# bot_base.net
KiCad netlist of a schematic drawn in EAGLE
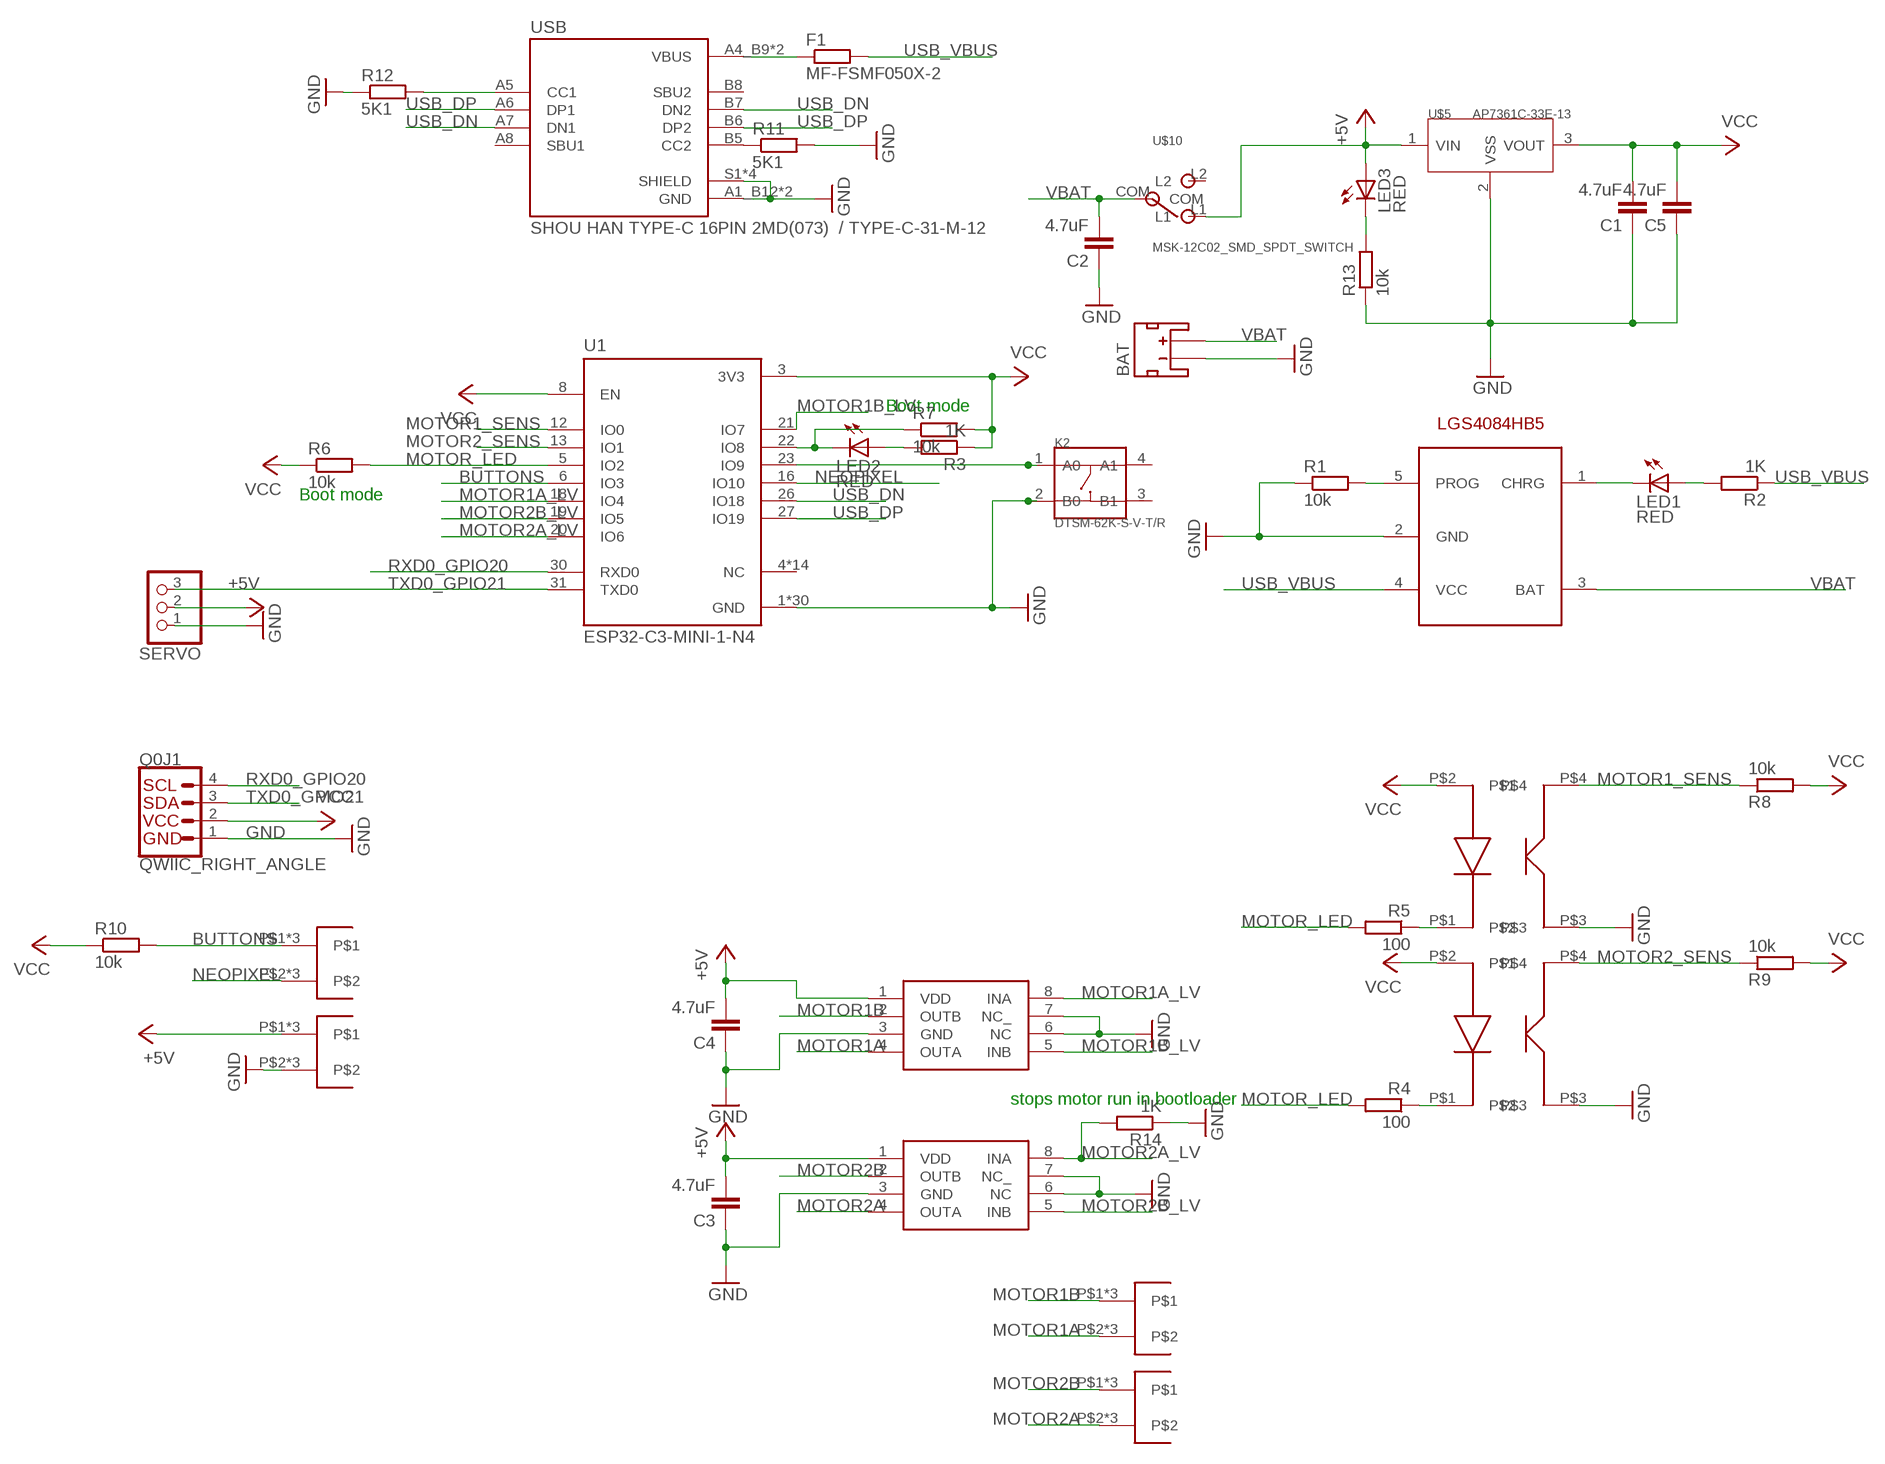
[diagram p0: schematic, sheet 1]

(export (version "E")
  (design (tool "Eeschema 10.0.6"))
  (components
    (comp (ref "BAT")
      (value "C47647 / S2B-PH-SM4-TB")
      (footprint "eagle-import:JST-2-SMD")
      (libsource (lib "eagle-import") (part "JST_2MM_MALE"))
    )
    (comp (ref "C1")
      (value "4.7uF")
      (footprint "eagle-import:C0805")
      (libsource (lib "eagle-import") (part "C-EUC0805"))
    )
    (comp (ref "C2")
      (value "4.7uF")
      (footprint "eagle-import:C0805")
      (libsource (lib "eagle-import") (part "C-EUC0805"))
    )
    (comp (ref "C3")
      (value "4.7uF")
      (footprint "eagle-import:C0805")
      (libsource (lib "eagle-import") (part "C-EUC0805"))
    )
    (comp (ref "C4")
      (value "4.7uF")
      (footprint "eagle-import:C0805")
      (libsource (lib "eagle-import") (part "C-EUC0805"))
    )
    (comp (ref "C5")
      (value "4.7uF")
      (footprint "eagle-import:C0805")
      (libsource (lib "eagle-import") (part "C-EUC0805"))
    )
    (comp (ref "F1")
      (value "MF-FSMF050X-2")
      (footprint "eagle-import:R0603")
      (libsource (lib "eagle-import") (part "R-EU_R0603"))
    )
    (comp (ref "K2")
      (value "DTSM-62K-S-V-T/R")
      (footprint "eagle-import:SW4-SMD-6.0X6.0X5.0MM")
      (libsource (lib "eagle-import") (part "SMD-SWITCH-TACTILE-SPST-NO(4P-D6.0MM)"))
    )
    (comp (ref "LED1")
      (value "RED")
      (footprint "eagle-import:CHIPLED_0603")
      (libsource (lib "eagle-import") (part "LEDCHIPLED_0603"))
    )
    (comp (ref "LED2")
      (value "RED")
      (footprint "eagle-import:CHIPLED_0603")
      (libsource (lib "eagle-import") (part "LEDCHIPLED_0603"))
    )
    (comp (ref "LED3")
      (value "RED")
      (footprint "eagle-import:CHIPLED_0603")
      (libsource (lib "eagle-import") (part "LEDCHIPLED_0603"))
    )
    (comp (ref "Q0")
      (value "QWIIC_RIGHT_ANGLE")
      (footprint "eagle-import:JST04_1MM_RA")
      (libsource (lib "eagle-import") (part "QWIIC_CONNECTORJS-1MM"))
    )
    (comp (ref "R1")
      (value "10k")
      (footprint "eagle-import:R0603")
      (libsource (lib "eagle-import") (part "R-EU_R0603"))
    )
    (comp (ref "R2")
      (value "1K")
      (footprint "eagle-import:R0603")
      (libsource (lib "eagle-import") (part "R-EU_R0603"))
    )
    (comp (ref "R3")
      (value "1K")
      (footprint "eagle-import:R0603")
      (libsource (lib "eagle-import") (part "R-EU_R0603"))
    )
    (comp (ref "R4")
      (value "100")
      (footprint "eagle-import:R0603")
      (libsource (lib "eagle-import") (part "R-EU_R0603"))
    )
    (comp (ref "R5")
      (value "100")
      (footprint "eagle-import:R0603")
      (libsource (lib "eagle-import") (part "R-EU_R0603"))
    )
    (comp (ref "R6")
      (value "10k")
      (footprint "eagle-import:R0603")
      (libsource (lib "eagle-import") (part "R-EU_R0603"))
    )
    (comp (ref "R7")
      (value "10k")
      (footprint "eagle-import:R0603")
      (libsource (lib "eagle-import") (part "R-EU_R0603"))
    )
    (comp (ref "R8")
      (value "10k")
      (footprint "eagle-import:R0603")
      (libsource (lib "eagle-import") (part "R-EU_R0603"))
    )
    (comp (ref "R9")
      (value "10k")
      (footprint "eagle-import:R0603")
      (libsource (lib "eagle-import") (part "R-EU_R0603"))
    )
    (comp (ref "R10")
      (value "10k")
      (footprint "eagle-import:R0603")
      (libsource (lib "eagle-import") (part "R-EU_R0603"))
    )
    (comp (ref "R11")
      (value "5K1")
      (footprint "eagle-import:R0603")
      (libsource (lib "eagle-import") (part "R-EU_R0603"))
    )
    (comp (ref "R12")
      (value "5K1")
      (footprint "eagle-import:R0603")
      (libsource (lib "eagle-import") (part "R-EU_R0603"))
    )
    (comp (ref "R13")
      (value "10k")
      (footprint "eagle-import:R0603")
      (libsource (lib "eagle-import") (part "R-EU_R0603"))
    )
    (comp (ref "R14")
      (value "1K")
      (footprint "eagle-import:R0603")
      (libsource (lib "eagle-import") (part "R-EU_R0603"))
    )
    (comp (ref "SERVO")
      (value "PINHD-1X03_2.54-S")
      (footprint "eagle-import:1X03-S")
      (libsource (lib "eagle-import") (part "PINHD-1X03_2.54-S"))
    )
    (comp (ref "U$1")
      (value "XL-ITR9707")
      (footprint "eagle-import:XL-ITR9707")
      (libsource (lib "eagle-import") (part "XL-ITR9707"))
    )
    (comp (ref "U$2")
      (value "XL-ITR9707")
      (footprint "eagle-import:XL-ITR9707")
      (libsource (lib "eagle-import") (part "XL-ITR9707"))
    )
    (comp (ref "U$3")
      (value "GR6205")
      (footprint "eagle-import:SOP8")
      (libsource (lib "eagle-import") (part "GR6205"))
    )
    (comp (ref "U$4")
      (value "GR6205")
      (footprint "eagle-import:SOP8")
      (libsource (lib "eagle-import") (part "GR6205"))
    )
    (comp (ref "U$5")
      (value "AP7361C-33E-13")
      (footprint "eagle-import:SOT223")
      (libsource (lib "eagle-import") (part "AP7361C-33E-13"))
    )
    (comp (ref "U$6")
      (value "PCBSIDE2")
      (footprint "eagle-import:PCBSIDE2")
      (libsource (lib "eagle-import") (part "PCBSIDE2"))
    )
    (comp (ref "U$7")
      (value "PCBSIDE2")
      (footprint "eagle-import:PCBSIDE2")
      (libsource (lib "eagle-import") (part "PCBSIDE2"))
    )
    (comp (ref "U$8")
      (value "PCBSIDE2")
      (footprint "eagle-import:PCBSIDE2")
      (libsource (lib "eagle-import") (part "PCBSIDE2"))
    )
    (comp (ref "U$9")
      (value "PCBSIDE2")
      (footprint "eagle-import:PCBSIDE2")
      (libsource (lib "eagle-import") (part "PCBSIDE2"))
    )
    (comp (ref "U$10")
      (value "MSK-12C02_SMD_SPDT_SWITCH")
      (footprint "eagle-import:MSK-12C02")
      (libsource (lib "eagle-import") (part "MSK-12C02_SMD_SPDT_SWITCH"))
    )
    (comp (ref "U1")
      (value "ESP32-C3-MINI-1-N4")
      (footprint "eagle-import:XCVR_ESP32-C3-MINI-1-N4")
      (fields (field (name "MF") "Espressif Systems"))
      (libsource (lib "eagle-import") (part "ESP32-C3-MINI-1-N4"))
    )
    (comp (ref "U4")
      (value "LGS4084HB5")
      (footprint "eagle-import:SOT23-5")
      (libsource (lib "eagle-import") (part "LGS4084HB5"))
    )
    (comp (ref "USB")
      (value "SHOU HAN TYPE-C 16PIN 2MD(073) / TYPE-C-31-M-12")
      (footprint "eagle-import:HRO_TYPE-C-31-M-12")
      (fields (field (name "MF") "HRO Electronics Co., Ltd.") (field (name "MP") "TYPE-C-31-M-12"))
      (libsource (lib "eagle-import") (part "TYPE-C-31-M-12"))
    )
  )
  (nets
    (net (code "1") (name "+5V") (class "Default")
      (node (ref "C3") (pin "2") (pinfunction "2_2") (pintype "passive"))
      (node (ref "C4") (pin "2") (pinfunction "2_2") (pintype "passive"))
      (node (ref "LED3") (pin "A") (pinfunction "A_A") (pintype "passive"))
      (node (ref "SERVO") (pin "2") (pinfunction "2_2") (pintype "passive"))
      (node (ref "U$10") (pin "L1") (pinfunction "L1_L1") (pintype "bidirectional"))
      (node (ref "U$3") (pin "1") (pinfunction "VDD_1") (pintype "bidirectional"))
      (node (ref "U$4") (pin "1") (pinfunction "VDD_1") (pintype "bidirectional"))
      (node (ref "U$5") (pin "1") (pinfunction "VIN_1") (pintype "input"))
      (node (ref "U$9") (pin "P$1") (pinfunction "P$1_P$1") (pintype "bidirectional"))
      (node (ref "U$9") (pin "P$3") (pinfunction "P$1_P$3") (pintype "bidirectional"))
      (node (ref "U$9") (pin "P$4") (pinfunction "P$1_P$4") (pintype "bidirectional"))
    )
    (net (code "2") (name "/BUTTONS") (class "Default")
      (node (ref "R10") (pin "2") (pinfunction "2_2") (pintype "passive"))
      (node (ref "U$8") (pin "P$1") (pinfunction "P$1_P$1") (pintype "bidirectional"))
      (node (ref "U$8") (pin "P$3") (pinfunction "P$1_P$3") (pintype "bidirectional"))
      (node (ref "U$8") (pin "P$4") (pinfunction "P$1_P$4") (pintype "bidirectional"))
      (node (ref "U1") (pin "6") (pinfunction "IO3_6") (pintype "bidirectional"))
    )
    (net (code "3") (name "/MOTOR1A") (class "Default")
      (node (ref "U$3") (pin "4") (pinfunction "OUTA_4") (pintype "bidirectional"))
      (node (ref "U$6") (pin "P$2") (pinfunction "P$2_P$2") (pintype "bidirectional"))
      (node (ref "U$6") (pin "P$5") (pinfunction "P$2_P$5") (pintype "bidirectional"))
      (node (ref "U$6") (pin "P$6") (pinfunction "P$2_P$6") (pintype "bidirectional"))
    )
    (net (code "4") (name "/MOTOR1A_LV") (class "Default")
      (node (ref "U$3") (pin "8") (pinfunction "INA_8") (pintype "bidirectional"))
      (node (ref "U1") (pin "18") (pinfunction "IO4_18") (pintype "bidirectional"))
    )
    (net (code "5") (name "/MOTOR1B") (class "Default")
      (node (ref "U$3") (pin "2") (pinfunction "OUTB_2") (pintype "bidirectional"))
      (node (ref "U$6") (pin "P$1") (pinfunction "P$1_P$1") (pintype "bidirectional"))
      (node (ref "U$6") (pin "P$3") (pinfunction "P$1_P$3") (pintype "bidirectional"))
      (node (ref "U$6") (pin "P$4") (pinfunction "P$1_P$4") (pintype "bidirectional"))
    )
    (net (code "6") (name "/MOTOR1B_LV") (class "Default")
      (node (ref "U$3") (pin "5") (pinfunction "INB_5") (pintype "bidirectional"))
      (node (ref "U1") (pin "21") (pinfunction "IO7_21") (pintype "bidirectional"))
    )
    (net (code "7") (name "/MOTOR1_SENS") (class "Default")
      (node (ref "R8") (pin "1") (pinfunction "1_1") (pintype "passive"))
      (node (ref "U$1") (pin "P$4") (pinfunction "P$4_P$4") (pintype "bidirectional"))
      (node (ref "U1") (pin "12") (pinfunction "IO0_12") (pintype "bidirectional"))
    )
    (net (code "8") (name "/MOTOR2A") (class "Default")
      (node (ref "U$4") (pin "4") (pinfunction "OUTA_4") (pintype "bidirectional"))
      (node (ref "U$7") (pin "P$2") (pinfunction "P$2_P$2") (pintype "bidirectional"))
      (node (ref "U$7") (pin "P$5") (pinfunction "P$2_P$5") (pintype "bidirectional"))
      (node (ref "U$7") (pin "P$6") (pinfunction "P$2_P$6") (pintype "bidirectional"))
    )
    (net (code "9") (name "/MOTOR2A_LV") (class "Default")
      (node (ref "R14") (pin "2") (pinfunction "2_2") (pintype "passive"))
      (node (ref "U$4") (pin "8") (pinfunction "INA_8") (pintype "bidirectional"))
      (node (ref "U1") (pin "20") (pinfunction "IO6_20") (pintype "bidirectional"))
    )
    (net (code "10") (name "/MOTOR2B") (class "Default")
      (node (ref "U$4") (pin "2") (pinfunction "OUTB_2") (pintype "bidirectional"))
      (node (ref "U$7") (pin "P$1") (pinfunction "P$1_P$1") (pintype "bidirectional"))
      (node (ref "U$7") (pin "P$3") (pinfunction "P$1_P$3") (pintype "bidirectional"))
      (node (ref "U$7") (pin "P$4") (pinfunction "P$1_P$4") (pintype "bidirectional"))
    )
    (net (code "11") (name "/MOTOR2B_LV") (class "Default")
      (node (ref "U$4") (pin "5") (pinfunction "INB_5") (pintype "bidirectional"))
      (node (ref "U1") (pin "19") (pinfunction "IO5_19") (pintype "bidirectional"))
    )
    (net (code "12") (name "/MOTOR2_SENS") (class "Default")
      (node (ref "R9") (pin "1") (pinfunction "1_1") (pintype "passive"))
      (node (ref "U$2") (pin "P$4") (pinfunction "P$4_P$4") (pintype "bidirectional"))
      (node (ref "U1") (pin "13") (pinfunction "IO1_13") (pintype "bidirectional"))
    )
    (net (code "13") (name "/MOTOR_LED") (class "Default")
      (node (ref "R4") (pin "2") (pinfunction "2_2") (pintype "passive"))
      (node (ref "R5") (pin "2") (pinfunction "2_2") (pintype "passive"))
      (node (ref "R6") (pin "2") (pinfunction "2_2") (pintype "passive"))
      (node (ref "U1") (pin "5") (pinfunction "IO2_5") (pintype "bidirectional"))
    )
    (net (code "14") (name "/NEOPIXEL") (class "Default")
      (node (ref "U$8") (pin "P$2") (pinfunction "P$2_P$2") (pintype "bidirectional"))
      (node (ref "U$8") (pin "P$5") (pinfunction "P$2_P$5") (pintype "bidirectional"))
      (node (ref "U$8") (pin "P$6") (pinfunction "P$2_P$6") (pintype "bidirectional"))
      (node (ref "U1") (pin "16") (pinfunction "IO10_16") (pintype "bidirectional"))
    )
    (net (code "15") (name "/RXD0_GPIO20") (class "Default")
      (node (ref "Q0") (pin "4") (pinfunction "4_4") (pintype "passive"))
      (node (ref "U1") (pin "30") (pinfunction "RXD0_30") (pintype "bidirectional"))
    )
    (net (code "16") (name "/TXD0_GPIO21") (class "Default")
      (node (ref "Q0") (pin "3") (pinfunction "3_3") (pintype "passive"))
      (node (ref "SERVO") (pin "3") (pinfunction "3_3") (pintype "passive"))
      (node (ref "U1") (pin "31") (pinfunction "TXD0_31") (pintype "bidirectional"))
    )
    (net (code "17") (name "/USB_DN") (class "Default")
      (node (ref "U1") (pin "26") (pinfunction "IO18_26") (pintype "bidirectional"))
      (node (ref "USB") (pin "A7") (pinfunction "DN1_A7") (pintype "bidirectional"))
      (node (ref "USB") (pin "B7") (pinfunction "DN2_B7") (pintype "bidirectional"))
    )
    (net (code "18") (name "/USB_DP") (class "Default")
      (node (ref "U1") (pin "27") (pinfunction "IO19_27") (pintype "bidirectional"))
      (node (ref "USB") (pin "A6") (pinfunction "DP1_A6") (pintype "bidirectional"))
      (node (ref "USB") (pin "B6") (pinfunction "DP2_B6") (pintype "bidirectional"))
    )
    (net (code "19") (name "/USB_VBUS") (class "Default")
      (node (ref "F1") (pin "2") (pinfunction "2_2") (pintype "passive"))
      (node (ref "R2") (pin "1") (pinfunction "1_1") (pintype "passive"))
      (node (ref "U4") (pin "4") (pinfunction "VCC_4") (pintype "bidirectional"))
    )
    (net (code "20") (name "/VBAT") (class "Default")
      (node (ref "BAT") (pin "2") (pinfunction "+_2") (pintype "bidirectional"))
      (node (ref "C2") (pin "2") (pinfunction "2_2") (pintype "passive"))
      (node (ref "U$10") (pin "COM") (pinfunction "COM_COM") (pintype "bidirectional"))
      (node (ref "U4") (pin "3") (pinfunction "BAT_3") (pintype "bidirectional"))
    )
    (net (code "21") (name "GND") (class "Default")
      (node (ref "BAT") (pin "1") (pinfunction "-_1") (pintype "bidirectional"))
      (node (ref "C1") (pin "1") (pinfunction "1_1") (pintype "passive"))
      (node (ref "C2") (pin "1") (pinfunction "1_1") (pintype "passive"))
      (node (ref "C3") (pin "1") (pinfunction "1_1") (pintype "passive"))
      (node (ref "C4") (pin "1") (pinfunction "1_1") (pintype "passive"))
      (node (ref "C5") (pin "1") (pinfunction "1_1") (pintype "passive"))
      (node (ref "K2") (pin "2") (pinfunction "B0_2") (pintype "bidirectional"))
      (node (ref "Q0") (pin "1") (pinfunction "1_1") (pintype "power_in"))
      (node (ref "R1") (pin "1") (pinfunction "1_1") (pintype "passive"))
      (node (ref "R11") (pin "2") (pinfunction "2_2") (pintype "passive"))
      (node (ref "R12") (pin "1") (pinfunction "1_1") (pintype "passive"))
      (node (ref "R13") (pin "1") (pinfunction "1_1") (pintype "passive"))
      (node (ref "R14") (pin "1") (pinfunction "1_1") (pintype "passive"))
      (node (ref "SERVO") (pin "1") (pinfunction "1_1") (pintype "passive"))
      (node (ref "U$1") (pin "P$3") (pinfunction "P$3_P$3") (pintype "bidirectional"))
      (node (ref "U$2") (pin "P$3") (pinfunction "P$3_P$3") (pintype "bidirectional"))
      (node (ref "U$3") (pin "3") (pinfunction "GND_3") (pintype "bidirectional"))
      (node (ref "U$3") (pin "6") (pinfunction "NC_6") (pintype "bidirectional"))
      (node (ref "U$3") (pin "7") (pinfunction "NC__7") (pintype "bidirectional"))
      (node (ref "U$4") (pin "3") (pinfunction "GND_3") (pintype "bidirectional"))
      (node (ref "U$4") (pin "6") (pinfunction "NC_6") (pintype "bidirectional"))
      (node (ref "U$4") (pin "7") (pinfunction "NC__7") (pintype "bidirectional"))
      (node (ref "U$5") (pin "2") (pinfunction "VSS_2") (pintype "power_in"))
      (node (ref "U$9") (pin "P$2") (pinfunction "P$2_P$2") (pintype "bidirectional"))
      (node (ref "U$9") (pin "P$5") (pinfunction "P$2_P$5") (pintype "bidirectional"))
      (node (ref "U$9") (pin "P$6") (pinfunction "P$2_P$6") (pintype "bidirectional"))
      (node (ref "U1") (pin "1") (pinfunction "GND_1") (pintype "power_in"))
      (node (ref "U1") (pin "11") (pinfunction "GND_11") (pintype "power_in"))
      (node (ref "U1") (pin "14") (pinfunction "GND_14") (pintype "power_in"))
      (node (ref "U1") (pin "2") (pinfunction "GND_2") (pintype "power_in"))
      (node (ref "U1") (pin "36") (pinfunction "GND_36") (pintype "power_in"))
      (node (ref "U1") (pin "37") (pinfunction "GND_37") (pintype "power_in"))
      (node (ref "U1") (pin "38") (pinfunction "GND_38") (pintype "power_in"))
      (node (ref "U1") (pin "39") (pinfunction "GND_39") (pintype "power_in"))
      (node (ref "U1") (pin "40") (pinfunction "GND_40") (pintype "power_in"))
      (node (ref "U1") (pin "41") (pinfunction "GND_41") (pintype "power_in"))
      (node (ref "U1") (pin "42") (pinfunction "GND_42") (pintype "power_in"))
      (node (ref "U1") (pin "43") (pinfunction "GND_43") (pintype "power_in"))
      (node (ref "U1") (pin "44") (pinfunction "GND_44") (pintype "power_in"))
      (node (ref "U1") (pin "45") (pinfunction "GND_45") (pintype "power_in"))
      (node (ref "U1") (pin "46") (pinfunction "GND_46") (pintype "power_in"))
      (node (ref "U1") (pin "47") (pinfunction "GND_47") (pintype "power_in"))
      (node (ref "U1") (pin "48") (pinfunction "GND_48") (pintype "power_in"))
      (node (ref "U1") (pin "49_1") (pinfunction "GND_49_1") (pintype "power_in"))
      (node (ref "U1") (pin "49_2") (pinfunction "GND_49_2") (pintype "power_in"))
      (node (ref "U1") (pin "49_3") (pinfunction "GND_49_3") (pintype "power_in"))
      (node (ref "U1") (pin "49_4") (pinfunction "GND_49_4") (pintype "power_in"))
      (node (ref "U1") (pin "49_5") (pinfunction "GND_49_5") (pintype "power_in"))
      (node (ref "U1") (pin "49_6") (pinfunction "GND_49_6") (pintype "power_in"))
      (node (ref "U1") (pin "49_7") (pinfunction "GND_49_7") (pintype "power_in"))
      (node (ref "U1") (pin "49_8") (pinfunction "GND_49_8") (pintype "power_in"))
      (node (ref "U1") (pin "49_9") (pinfunction "GND_49_9") (pintype "power_in"))
      (node (ref "U1") (pin "50") (pinfunction "GND_50") (pintype "power_in"))
      (node (ref "U1") (pin "51") (pinfunction "GND_51") (pintype "power_in"))
      (node (ref "U1") (pin "52") (pinfunction "GND_52") (pintype "power_in"))
      (node (ref "U1") (pin "53") (pinfunction "GND_53") (pintype "power_in"))
      (node (ref "U4") (pin "2") (pinfunction "GND_2") (pintype "bidirectional"))
      (node (ref "USB") (pin "A1_B12") (pinfunction "GND_A1_B12") (pintype "power_in"))
      (node (ref "USB") (pin "B1_A12") (pinfunction "GND_B1_A12") (pintype "power_in"))
      (node (ref "USB") (pin "S1") (pinfunction "SHIELD_S1") (pintype "passive"))
      (node (ref "USB") (pin "S2") (pinfunction "SHIELD_S2") (pintype "passive"))
      (node (ref "USB") (pin "S3") (pinfunction "SHIELD_S3") (pintype "passive"))
      (node (ref "USB") (pin "S4") (pinfunction "SHIELD_S4") (pintype "passive"))
    )
    (net (code "22") (name "Net-(F1-Pad1)") (class "Default")
      (node (ref "F1") (pin "1") (pinfunction "1_1") (pintype "passive"))
      (node (ref "USB") (pin "A4_B9") (pinfunction "VBUS_A4_B9") (pintype "power_in"))
      (node (ref "USB") (pin "B4_A9") (pinfunction "VBUS_B4_A9") (pintype "power_in"))
    )
    (net (code "23") (name "Net-(K2-A0)") (class "Default")
      (node (ref "K2") (pin "1") (pinfunction "A0_1") (pintype "bidirectional"))
      (node (ref "U1") (pin "23") (pinfunction "IO9_23") (pintype "bidirectional"))
    )
    (net (code "24") (name "Net-(LED1-PadA)") (class "Default")
      (node (ref "LED1") (pin "A") (pinfunction "A_A") (pintype "passive"))
      (node (ref "R2") (pin "2") (pinfunction "2_2") (pintype "passive"))
    )
    (net (code "25") (name "Net-(LED2-PadA)") (class "Default")
      (node (ref "LED2") (pin "A") (pinfunction "A_A") (pintype "passive"))
      (node (ref "R3") (pin "2") (pinfunction "2_2") (pintype "passive"))
    )
    (net (code "26") (name "Net-(LED3-PadC)") (class "Default")
      (node (ref "LED3") (pin "C") (pinfunction "C_C") (pintype "passive"))
      (node (ref "R13") (pin "2") (pinfunction "2_2") (pintype "passive"))
    )
    (net (code "27") (name "Net-(U$1-P$2)") (class "Default")
      (node (ref "R5") (pin "1") (pinfunction "1_1") (pintype "passive"))
      (node (ref "U$1") (pin "P$1") (pinfunction "P$2_P$1") (pintype "bidirectional"))
    )
    (net (code "28") (name "Net-(U$2-P$2)") (class "Default")
      (node (ref "R4") (pin "1") (pinfunction "1_1") (pintype "passive"))
      (node (ref "U$2") (pin "P$1") (pinfunction "P$2_P$1") (pintype "bidirectional"))
    )
    (net (code "29") (name "Net-(U1-IO8)") (class "Default")
      (node (ref "LED2") (pin "C") (pinfunction "C_C") (pintype "passive"))
      (node (ref "R7") (pin "1") (pinfunction "1_1") (pintype "passive"))
      (node (ref "U1") (pin "22") (pinfunction "IO8_22") (pintype "bidirectional"))
    )
    (net (code "30") (name "Net-(U4-CHRG)") (class "Default")
      (node (ref "LED1") (pin "C") (pinfunction "C_C") (pintype "passive"))
      (node (ref "U4") (pin "1") (pinfunction "CHRG_1") (pintype "bidirectional"))
    )
    (net (code "31") (name "Net-(U4-PROG)") (class "Default")
      (node (ref "R1") (pin "2") (pinfunction "2_2") (pintype "passive"))
      (node (ref "U4") (pin "5") (pinfunction "PROG_5") (pintype "bidirectional"))
    )
    (net (code "32") (name "Net-(USB-CC1)") (class "Default")
      (node (ref "R12") (pin "2") (pinfunction "2_2") (pintype "passive"))
      (node (ref "USB") (pin "A5") (pinfunction "CC1_A5") (pintype "bidirectional"))
    )
    (net (code "33") (name "Net-(USB-CC2)") (class "Default")
      (node (ref "R11") (pin "1") (pinfunction "1_1") (pintype "passive"))
      (node (ref "USB") (pin "B5") (pinfunction "CC2_B5") (pintype "bidirectional"))
    )
    (net (code "34") (name "VCC") (class "Default")
      (node (ref "C1") (pin "2") (pinfunction "2_2") (pintype "passive"))
      (node (ref "C5") (pin "2") (pinfunction "2_2") (pintype "passive"))
      (node (ref "Q0") (pin "2") (pinfunction "2_2") (pintype "power_in"))
      (node (ref "R10") (pin "1") (pinfunction "1_1") (pintype "passive"))
      (node (ref "R3") (pin "1") (pinfunction "1_1") (pintype "passive"))
      (node (ref "R6") (pin "1") (pinfunction "1_1") (pintype "passive"))
      (node (ref "R7") (pin "2") (pinfunction "2_2") (pintype "passive"))
      (node (ref "R8") (pin "2") (pinfunction "2_2") (pintype "passive"))
      (node (ref "R9") (pin "2") (pinfunction "2_2") (pintype "passive"))
      (node (ref "U$1") (pin "P$2") (pinfunction "P$1_P$2") (pintype "bidirectional"))
      (node (ref "U$2") (pin "P$2") (pinfunction "P$1_P$2") (pintype "bidirectional"))
      (node (ref "U$5") (pin "3") (pinfunction "VOUT_3") (pintype "output"))
      (node (ref "U1") (pin "3") (pinfunction "3V3_3") (pintype "power_in"))
      (node (ref "U1") (pin "8") (pinfunction "EN_8") (pintype "input"))
    )
    (net (code "35") (name "unconnected-(BAT-PAD1-PadNC1)") (class "Default")
      (node (ref "BAT") (pin "NC1") (pinfunction "PAD1_NC1") (pintype "bidirectional"))
    )
    (net (code "36") (name "unconnected-(BAT-PAD2-PadNC2)") (class "Default")
      (node (ref "BAT") (pin "NC2") (pinfunction "PAD2_NC2") (pintype "bidirectional"))
    )
    (net (code "37") (name "unconnected-(K2-A1-Pad4)") (class "Default")
      (node (ref "K2") (pin "4") (pinfunction "A1_4") (pintype "bidirectional"))
    )
    (net (code "38") (name "unconnected-(K2-B1-Pad3)") (class "Default")
      (node (ref "K2") (pin "3") (pinfunction "B1_3") (pintype "bidirectional"))
    )
    (net (code "39") (name "unconnected-(U$10-PadL2)") (class "Default")
      (node (ref "U$10") (pin "L2") (pinfunction "L2_L2") (pintype "bidirectional"))
    )
    (net (code "40") (name "unconnected-(U1-NC-Pad4)") (class "Default")
      (node (ref "U1") (pin "4") (pinfunction "NC_4") (pintype "no_connect"))
    )
    (net (code "41") (name "unconnected-(U1-NC-Pad7)") (class "Default")
      (node (ref "U1") (pin "7") (pinfunction "NC_7") (pintype "no_connect"))
    )
    (net (code "42") (name "unconnected-(U1-NC-Pad9)") (class "Default")
      (node (ref "U1") (pin "9") (pinfunction "NC_9") (pintype "no_connect"))
    )
    (net (code "43") (name "unconnected-(U1-NC-Pad10)") (class "Default")
      (node (ref "U1") (pin "10") (pinfunction "NC_10") (pintype "no_connect"))
    )
    (net (code "44") (name "unconnected-(U1-NC-Pad15)") (class "Default")
      (node (ref "U1") (pin "15") (pinfunction "NC_15") (pintype "no_connect"))
    )
    (net (code "45") (name "unconnected-(U1-NC-Pad17)") (class "Default")
      (node (ref "U1") (pin "17") (pinfunction "NC_17") (pintype "no_connect"))
    )
    (net (code "46") (name "unconnected-(U1-NC-Pad24)") (class "Default")
      (node (ref "U1") (pin "24") (pinfunction "NC_24") (pintype "no_connect"))
    )
    (net (code "47") (name "unconnected-(U1-NC-Pad25)") (class "Default")
      (node (ref "U1") (pin "25") (pinfunction "NC_25") (pintype "no_connect"))
    )
    (net (code "48") (name "unconnected-(U1-NC-Pad28)") (class "Default")
      (node (ref "U1") (pin "28") (pinfunction "NC_28") (pintype "no_connect"))
    )
    (net (code "49") (name "unconnected-(U1-NC-Pad29)") (class "Default")
      (node (ref "U1") (pin "29") (pinfunction "NC_29") (pintype "no_connect"))
    )
    (net (code "50") (name "unconnected-(U1-NC-Pad32)") (class "Default")
      (node (ref "U1") (pin "32") (pinfunction "NC_32") (pintype "no_connect"))
    )
    (net (code "51") (name "unconnected-(U1-NC-Pad33)") (class "Default")
      (node (ref "U1") (pin "33") (pinfunction "NC_33") (pintype "no_connect"))
    )
    (net (code "52") (name "unconnected-(U1-NC-Pad34)") (class "Default")
      (node (ref "U1") (pin "34") (pinfunction "NC_34") (pintype "no_connect"))
    )
    (net (code "53") (name "unconnected-(U1-NC-Pad35)") (class "Default")
      (node (ref "U1") (pin "35") (pinfunction "NC_35") (pintype "no_connect"))
    )
    (net (code "54") (name "unconnected-(USB-SBU1-PadA8)") (class "Default")
      (node (ref "USB") (pin "A8") (pinfunction "SBU1_A8") (pintype "bidirectional"))
    )
    (net (code "55") (name "unconnected-(USB-SBU2-PadB8)") (class "Default")
      (node (ref "USB") (pin "B8") (pinfunction "SBU2_B8") (pintype "bidirectional"))
    )
  )
)
